# smd-reflow-2-rendered.net
KiCad netlist of a schematic drawn in EAGLE
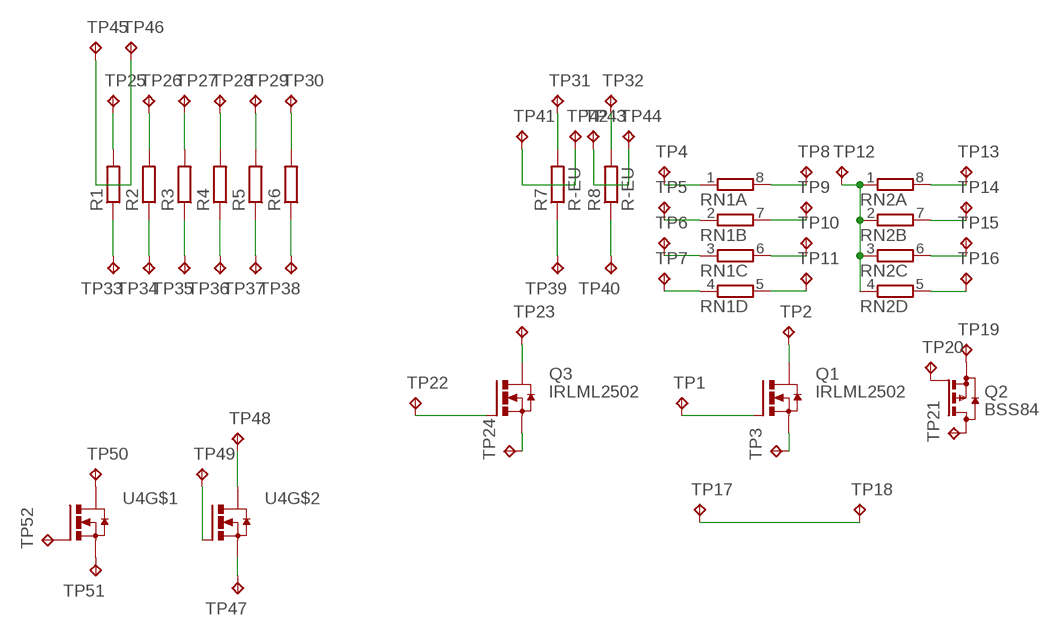
[diagram p0: schematic, sheet 1]

(export (version "E")
  (design (tool "Eeschema 10.0.6"))
  (components
    (comp (ref "Q1")
      (value "IRLML2502")
      (footprint "eagle-import:MICRO3")
      (libsource (lib "eagle-import") (part "IRLML2502"))
    )
    (comp (ref "Q2")
      (value "BSS84")
      (footprint "eagle-import:SOT23")
      (libsource (lib "eagle-import") (part "BSS84"))
    )
    (comp (ref "Q3")
      (value "IRLML2502")
      (footprint "eagle-import:MICRO3")
      (libsource (lib "eagle-import") (part "IRLML2502"))
    )
    (comp (ref "R1")
      (value "R-EU_R0603")
      (footprint "eagle-import:R0603")
      (libsource (lib "eagle-import") (part "R-EU_R0603"))
    )
    (comp (ref "R2")
      (value "R-EU_R0603")
      (footprint "eagle-import:R0603")
      (libsource (lib "eagle-import") (part "R-EU_R0603"))
    )
    (comp (ref "R3")
      (value "R-EU_R0805")
      (footprint "eagle-import:R0805")
      (libsource (lib "eagle-import") (part "R-EU_R0805"))
    )
    (comp (ref "R4")
      (value "R-EU_R0805")
      (footprint "eagle-import:R0805")
      (libsource (lib "eagle-import") (part "R-EU_R0805"))
    )
    (comp (ref "R5")
      (value "R-EU_R0805W")
      (footprint "eagle-import:R0805W")
      (libsource (lib "eagle-import") (part "R-EU_R0805W"))
    )
    (comp (ref "R6")
      (value "R-EU_R0805W")
      (footprint "eagle-import:R0805W")
      (libsource (lib "eagle-import") (part "R-EU_R0805W"))
    )
    (comp (ref "R7")
      (value "R-EU")
      (footprint "eagle-import:R0805H")
      (libsource (lib "eagle-import") (part "R-EU"))
    )
    (comp (ref "R8")
      (value "R-EU")
      (footprint "eagle-import:R0805H")
      (libsource (lib "eagle-import") (part "R-EU"))
    )
    (comp (ref "RN1")
      (value "4R-NEXB38V")
      (footprint "eagle-import:EXB38V")
      (libsource (lib "eagle-import") (part "4R-NEXB38V"))
    )
    (comp (ref "RN2")
      (value "4R-NEXB38V")
      (footprint "eagle-import:EXB38V")
      (libsource (lib "eagle-import") (part "4R-NEXB38V"))
    )
    (comp (ref "TP1")
      (value "TPB1,27")
      (footprint "eagle-import:B1,27")
      (libsource (lib "eagle-import") (part "TPB1,27"))
    )
    (comp (ref "TP2")
      (value "TPB1,27")
      (footprint "eagle-import:B1,27")
      (libsource (lib "eagle-import") (part "TPB1,27"))
    )
    (comp (ref "TP3")
      (value "TPB1,27")
      (footprint "eagle-import:B1,27")
      (libsource (lib "eagle-import") (part "TPB1,27"))
    )
    (comp (ref "TP4")
      (value "TPB1,27")
      (footprint "eagle-import:B1,27")
      (libsource (lib "eagle-import") (part "TPB1,27"))
    )
    (comp (ref "TP5")
      (value "TPB1,27")
      (footprint "eagle-import:B1,27")
      (libsource (lib "eagle-import") (part "TPB1,27"))
    )
    (comp (ref "TP6")
      (value "TPB1,27")
      (footprint "eagle-import:B1,27")
      (libsource (lib "eagle-import") (part "TPB1,27"))
    )
    (comp (ref "TP7")
      (value "TPB1,27")
      (footprint "eagle-import:B1,27")
      (libsource (lib "eagle-import") (part "TPB1,27"))
    )
    (comp (ref "TP8")
      (value "TPB1,27")
      (footprint "eagle-import:B1,27")
      (libsource (lib "eagle-import") (part "TPB1,27"))
    )
    (comp (ref "TP9")
      (value "TPB1,27")
      (footprint "eagle-import:B1,27")
      (libsource (lib "eagle-import") (part "TPB1,27"))
    )
    (comp (ref "TP10")
      (value "TPB1,27")
      (footprint "eagle-import:B1,27")
      (libsource (lib "eagle-import") (part "TPB1,27"))
    )
    (comp (ref "TP11")
      (value "TPB1,27")
      (footprint "eagle-import:B1,27")
      (libsource (lib "eagle-import") (part "TPB1,27"))
    )
    (comp (ref "TP12")
      (value "TPB1,27")
      (footprint "eagle-import:B1,27")
      (libsource (lib "eagle-import") (part "TPB1,27"))
    )
    (comp (ref "TP13")
      (value "TPB1,27")
      (footprint "eagle-import:B1,27")
      (libsource (lib "eagle-import") (part "TPB1,27"))
    )
    (comp (ref "TP14")
      (value "TPB1,27")
      (footprint "eagle-import:B1,27")
      (libsource (lib "eagle-import") (part "TPB1,27"))
    )
    (comp (ref "TP15")
      (value "TPB1,27")
      (footprint "eagle-import:B1,27")
      (libsource (lib "eagle-import") (part "TPB1,27"))
    )
    (comp (ref "TP16")
      (value "TPB1,27")
      (footprint "eagle-import:B1,27")
      (libsource (lib "eagle-import") (part "TPB1,27"))
    )
    (comp (ref "TP17")
      (value "TPB1,27")
      (footprint "eagle-import:B1,27")
      (libsource (lib "eagle-import") (part "TPB1,27"))
    )
    (comp (ref "TP18")
      (value "TPB1,27")
      (footprint "eagle-import:B1,27")
      (libsource (lib "eagle-import") (part "TPB1,27"))
    )
    (comp (ref "TP19")
      (value "TPB1,27")
      (footprint "eagle-import:B1,27")
      (libsource (lib "eagle-import") (part "TPB1,27"))
    )
    (comp (ref "TP20")
      (value "TPB1,27")
      (footprint "eagle-import:B1,27")
      (libsource (lib "eagle-import") (part "TPB1,27"))
    )
    (comp (ref "TP21")
      (value "TPB1,27")
      (footprint "eagle-import:B1,27")
      (libsource (lib "eagle-import") (part "TPB1,27"))
    )
    (comp (ref "TP22")
      (value "TPB1,27")
      (footprint "eagle-import:B1,27")
      (libsource (lib "eagle-import") (part "TPB1,27"))
    )
    (comp (ref "TP23")
      (value "TPB1,27")
      (footprint "eagle-import:B1,27")
      (libsource (lib "eagle-import") (part "TPB1,27"))
    )
    (comp (ref "TP24")
      (value "TPB1,27")
      (footprint "eagle-import:B1,27")
      (libsource (lib "eagle-import") (part "TPB1,27"))
    )
    (comp (ref "TP25")
      (value "TPB1,27")
      (footprint "eagle-import:B1,27")
      (libsource (lib "eagle-import") (part "TPB1,27"))
    )
    (comp (ref "TP26")
      (value "TPB1,27")
      (footprint "eagle-import:B1,27")
      (libsource (lib "eagle-import") (part "TPB1,27"))
    )
    (comp (ref "TP27")
      (value "TPB1,27")
      (footprint "eagle-import:B1,27")
      (libsource (lib "eagle-import") (part "TPB1,27"))
    )
    (comp (ref "TP28")
      (value "TPB1,27")
      (footprint "eagle-import:B1,27")
      (libsource (lib "eagle-import") (part "TPB1,27"))
    )
    (comp (ref "TP29")
      (value "TPB1,27")
      (footprint "eagle-import:B1,27")
      (libsource (lib "eagle-import") (part "TPB1,27"))
    )
    (comp (ref "TP30")
      (value "TPB1,27")
      (footprint "eagle-import:B1,27")
      (libsource (lib "eagle-import") (part "TPB1,27"))
    )
    (comp (ref "TP31")
      (value "TPB1,27")
      (footprint "eagle-import:B1,27")
      (libsource (lib "eagle-import") (part "TPB1,27"))
    )
    (comp (ref "TP32")
      (value "TPB1,27")
      (footprint "eagle-import:B1,27")
      (libsource (lib "eagle-import") (part "TPB1,27"))
    )
    (comp (ref "TP33")
      (value "TPB1,27")
      (footprint "eagle-import:B1,27")
      (libsource (lib "eagle-import") (part "TPB1,27"))
    )
    (comp (ref "TP34")
      (value "TPB1,27")
      (footprint "eagle-import:B1,27")
      (libsource (lib "eagle-import") (part "TPB1,27"))
    )
    (comp (ref "TP35")
      (value "TPB1,27")
      (footprint "eagle-import:B1,27")
      (libsource (lib "eagle-import") (part "TPB1,27"))
    )
    (comp (ref "TP36")
      (value "TPB1,27")
      (footprint "eagle-import:B1,27")
      (libsource (lib "eagle-import") (part "TPB1,27"))
    )
    (comp (ref "TP37")
      (value "TPB1,27")
      (footprint "eagle-import:B1,27")
      (libsource (lib "eagle-import") (part "TPB1,27"))
    )
    (comp (ref "TP38")
      (value "TPB1,27")
      (footprint "eagle-import:B1,27")
      (libsource (lib "eagle-import") (part "TPB1,27"))
    )
    (comp (ref "TP39")
      (value "TPB1,27")
      (footprint "eagle-import:B1,27")
      (libsource (lib "eagle-import") (part "TPB1,27"))
    )
    (comp (ref "TP40")
      (value "TPB1,27")
      (footprint "eagle-import:B1,27")
      (libsource (lib "eagle-import") (part "TPB1,27"))
    )
    (comp (ref "TP41")
      (value "TPB1,27")
      (footprint "eagle-import:B1,27")
      (libsource (lib "eagle-import") (part "TPB1,27"))
    )
    (comp (ref "TP42")
      (value "TPB1,27")
      (footprint "eagle-import:B1,27")
      (libsource (lib "eagle-import") (part "TPB1,27"))
    )
    (comp (ref "TP43")
      (value "TPB1,27")
      (footprint "eagle-import:B1,27")
      (libsource (lib "eagle-import") (part "TPB1,27"))
    )
    (comp (ref "TP44")
      (value "TPB1,27")
      (footprint "eagle-import:B1,27")
      (libsource (lib "eagle-import") (part "TPB1,27"))
    )
    (comp (ref "TP45")
      (value "TPB1,27")
      (footprint "eagle-import:B1,27")
      (libsource (lib "eagle-import") (part "TPB1,27"))
    )
    (comp (ref "TP46")
      (value "TPB1,27")
      (footprint "eagle-import:B1,27")
      (libsource (lib "eagle-import") (part "TPB1,27"))
    )
    (comp (ref "TP47")
      (value "TPB1,27")
      (footprint "eagle-import:B1,27")
      (libsource (lib "eagle-import") (part "TPB1,27"))
    )
    (comp (ref "TP48")
      (value "TPB1,27")
      (footprint "eagle-import:B1,27")
      (libsource (lib "eagle-import") (part "TPB1,27"))
    )
    (comp (ref "TP49")
      (value "TPB1,27")
      (footprint "eagle-import:B1,27")
      (libsource (lib "eagle-import") (part "TPB1,27"))
    )
    (comp (ref "TP50")
      (value "TPB1,27")
      (footprint "eagle-import:B1,27")
      (libsource (lib "eagle-import") (part "TPB1,27"))
    )
    (comp (ref "TP51")
      (value "TPB1,27")
      (footprint "eagle-import:B1,27")
      (libsource (lib "eagle-import") (part "TPB1,27"))
    )
    (comp (ref "TP52")
      (value "TPB1,27")
      (footprint "eagle-import:B1,27")
      (libsource (lib "eagle-import") (part "TPB1,27"))
    )
    (comp (ref "U4")
      (value "2N7002GW")
      (footprint "eagle-import:SOT363_INFINEON")
      (libsource (lib "eagle-import") (part "2N7002GW"))
    )
  )
  (nets
    (net (code "1") (name "Net-(Q1-D)") (class "Default")
      (node (ref "Q1") (pin "3") (pinfunction "D_3") (pintype "passive"))
      (node (ref "TP2") (pin "TP") (pinfunction "TP_TP") (pintype "input"))
    )
    (net (code "2") (name "Net-(Q1-G)") (class "Default")
      (node (ref "Q1") (pin "1") (pinfunction "G_1") (pintype "passive"))
      (node (ref "TP1") (pin "TP") (pinfunction "TP_TP") (pintype "input"))
    )
    (net (code "3") (name "Net-(Q1-S)") (class "Default")
      (node (ref "Q1") (pin "2") (pinfunction "S_2") (pintype "passive"))
      (node (ref "TP3") (pin "TP") (pinfunction "TP_TP") (pintype "input"))
    )
    (net (code "4") (name "Net-(Q2-D)") (class "Default")
      (node (ref "Q2") (pin "3") (pinfunction "D_3") (pintype "passive"))
      (node (ref "TP21") (pin "TP") (pinfunction "TP_TP") (pintype "input"))
    )
    (net (code "5") (name "Net-(Q2-G)") (class "Default")
      (node (ref "Q2") (pin "1") (pinfunction "G_1") (pintype "passive"))
      (node (ref "TP20") (pin "TP") (pinfunction "TP_TP") (pintype "input"))
    )
    (net (code "6") (name "Net-(Q2-S)") (class "Default")
      (node (ref "Q2") (pin "2") (pinfunction "S_2") (pintype "passive"))
      (node (ref "TP19") (pin "TP") (pinfunction "TP_TP") (pintype "input"))
    )
    (net (code "7") (name "Net-(Q3-D)") (class "Default")
      (node (ref "Q3") (pin "3") (pinfunction "D_3") (pintype "passive"))
      (node (ref "TP23") (pin "TP") (pinfunction "TP_TP") (pintype "input"))
    )
    (net (code "8") (name "Net-(Q3-G)") (class "Default")
      (node (ref "Q3") (pin "1") (pinfunction "G_1") (pintype "passive"))
      (node (ref "TP22") (pin "TP") (pinfunction "TP_TP") (pintype "input"))
    )
    (net (code "9") (name "Net-(Q3-S)") (class "Default")
      (node (ref "Q3") (pin "2") (pinfunction "S_2") (pintype "passive"))
      (node (ref "TP24") (pin "TP") (pinfunction "TP_TP") (pintype "input"))
    )
    (net (code "10") (name "Net-(R1-Pad1)") (class "Default")
      (node (ref "R1") (pin "1") (pinfunction "1_1") (pintype "passive"))
      (node (ref "TP33") (pin "TP") (pinfunction "TP_TP") (pintype "input"))
    )
    (net (code "11") (name "Net-(R1-Pad2)") (class "Default")
      (node (ref "R1") (pin "2") (pinfunction "2_2") (pintype "passive"))
      (node (ref "TP25") (pin "TP") (pinfunction "TP_TP") (pintype "input"))
    )
    (net (code "12") (name "Net-(R2-Pad1)") (class "Default")
      (node (ref "R2") (pin "1") (pinfunction "1_1") (pintype "passive"))
      (node (ref "TP34") (pin "TP") (pinfunction "TP_TP") (pintype "input"))
    )
    (net (code "13") (name "Net-(R2-Pad2)") (class "Default")
      (node (ref "R2") (pin "2") (pinfunction "2_2") (pintype "passive"))
      (node (ref "TP26") (pin "TP") (pinfunction "TP_TP") (pintype "input"))
    )
    (net (code "14") (name "Net-(R3-Pad1)") (class "Default")
      (node (ref "R3") (pin "1") (pinfunction "1_1") (pintype "passive"))
      (node (ref "TP35") (pin "TP") (pinfunction "TP_TP") (pintype "input"))
    )
    (net (code "15") (name "Net-(R3-Pad2)") (class "Default")
      (node (ref "R3") (pin "2") (pinfunction "2_2") (pintype "passive"))
      (node (ref "TP27") (pin "TP") (pinfunction "TP_TP") (pintype "input"))
    )
    (net (code "16") (name "Net-(R4-Pad1)") (class "Default")
      (node (ref "R4") (pin "1") (pinfunction "1_1") (pintype "passive"))
      (node (ref "TP36") (pin "TP") (pinfunction "TP_TP") (pintype "input"))
    )
    (net (code "17") (name "Net-(R4-Pad2)") (class "Default")
      (node (ref "R4") (pin "2") (pinfunction "2_2") (pintype "passive"))
      (node (ref "TP28") (pin "TP") (pinfunction "TP_TP") (pintype "input"))
    )
    (net (code "18") (name "Net-(R5-Pad1)") (class "Default")
      (node (ref "R5") (pin "1") (pinfunction "1_1") (pintype "passive"))
      (node (ref "TP37") (pin "TP") (pinfunction "TP_TP") (pintype "input"))
    )
    (net (code "19") (name "Net-(R5-Pad2)") (class "Default")
      (node (ref "R5") (pin "2") (pinfunction "2_2") (pintype "passive"))
      (node (ref "TP29") (pin "TP") (pinfunction "TP_TP") (pintype "input"))
    )
    (net (code "20") (name "Net-(R6-Pad1)") (class "Default")
      (node (ref "R6") (pin "1") (pinfunction "1_1") (pintype "passive"))
      (node (ref "TP38") (pin "TP") (pinfunction "TP_TP") (pintype "input"))
    )
    (net (code "21") (name "Net-(R6-Pad2)") (class "Default")
      (node (ref "R6") (pin "2") (pinfunction "2_2") (pintype "passive"))
      (node (ref "TP30") (pin "TP") (pinfunction "TP_TP") (pintype "input"))
    )
    (net (code "22") (name "Net-(R7-Pad1)") (class "Default")
      (node (ref "R7") (pin "1") (pinfunction "1_1") (pintype "passive"))
      (node (ref "TP39") (pin "TP") (pinfunction "TP_TP") (pintype "input"))
    )
    (net (code "23") (name "Net-(R7-Pad2)") (class "Default")
      (node (ref "R7") (pin "2") (pinfunction "2_2") (pintype "passive"))
      (node (ref "TP31") (pin "TP") (pinfunction "TP_TP") (pintype "input"))
    )
    (net (code "24") (name "Net-(R8-Pad1)") (class "Default")
      (node (ref "R8") (pin "1") (pinfunction "1_1") (pintype "passive"))
      (node (ref "TP40") (pin "TP") (pinfunction "TP_TP") (pintype "input"))
    )
    (net (code "25") (name "Net-(R8-Pad2)") (class "Default")
      (node (ref "R8") (pin "2") (pinfunction "2_2") (pintype "passive"))
      (node (ref "TP32") (pin "TP") (pinfunction "TP_TP") (pintype "input"))
    )
    (net (code "26") (name "Net-(RN1-Pad1)") (class "Default")
      (node (ref "RN1") (pin "1") (pinfunction "1_1") (pintype "passive"))
      (node (ref "TP4") (pin "TP") (pinfunction "TP_TP") (pintype "input"))
    )
    (net (code "27") (name "Net-(RN1A-2)") (class "Default")
      (node (ref "RN1") (pin "8") (pinfunction "2_8") (pintype "passive"))
      (node (ref "TP8") (pin "TP") (pinfunction "TP_TP") (pintype "input"))
    )
    (net (code "28") (name "Net-(RN1B-1)") (class "Default")
      (node (ref "RN1") (pin "2") (pinfunction "1_2") (pintype "passive"))
      (node (ref "TP5") (pin "TP") (pinfunction "TP_TP") (pintype "input"))
    )
    (net (code "29") (name "Net-(RN1B-2)") (class "Default")
      (node (ref "RN1") (pin "7") (pinfunction "2_7") (pintype "passive"))
      (node (ref "TP9") (pin "TP") (pinfunction "TP_TP") (pintype "input"))
    )
    (net (code "30") (name "Net-(RN1C-1)") (class "Default")
      (node (ref "RN1") (pin "3") (pinfunction "1_3") (pintype "passive"))
      (node (ref "TP6") (pin "TP") (pinfunction "TP_TP") (pintype "input"))
    )
    (net (code "31") (name "Net-(RN1C-2)") (class "Default")
      (node (ref "RN1") (pin "6") (pinfunction "2_6") (pintype "passive"))
      (node (ref "TP10") (pin "TP") (pinfunction "TP_TP") (pintype "input"))
    )
    (net (code "32") (name "Net-(RN1D-1)") (class "Default")
      (node (ref "RN1") (pin "4") (pinfunction "1_4") (pintype "passive"))
      (node (ref "TP7") (pin "TP") (pinfunction "TP_TP") (pintype "input"))
    )
    (net (code "33") (name "Net-(RN1D-2)") (class "Default")
      (node (ref "RN1") (pin "5") (pinfunction "2_5") (pintype "passive"))
      (node (ref "TP11") (pin "TP") (pinfunction "TP_TP") (pintype "input"))
    )
    (net (code "34") (name "Net-(RN2A-2)") (class "Default")
      (node (ref "RN2") (pin "8") (pinfunction "2_8") (pintype "passive"))
      (node (ref "TP13") (pin "TP") (pinfunction "TP_TP") (pintype "input"))
    )
    (net (code "35") (name "Net-(RN2B-1)") (class "Default")
      (node (ref "RN2") (pin "1") (pinfunction "1_1") (pintype "passive"))
      (node (ref "RN2") (pin "2") (pinfunction "1_2") (pintype "passive"))
      (node (ref "RN2") (pin "3") (pinfunction "1_3") (pintype "passive"))
      (node (ref "RN2") (pin "4") (pinfunction "1_4") (pintype "passive"))
      (node (ref "TP12") (pin "TP") (pinfunction "TP_TP") (pintype "input"))
    )
    (net (code "36") (name "Net-(RN2B-2)") (class "Default")
      (node (ref "RN2") (pin "7") (pinfunction "2_7") (pintype "passive"))
      (node (ref "TP14") (pin "TP") (pinfunction "TP_TP") (pintype "input"))
    )
    (net (code "37") (name "Net-(RN2C-2)") (class "Default")
      (node (ref "RN2") (pin "6") (pinfunction "2_6") (pintype "passive"))
      (node (ref "TP15") (pin "TP") (pinfunction "TP_TP") (pintype "input"))
    )
    (net (code "38") (name "Net-(RN2D-2)") (class "Default")
      (node (ref "RN2") (pin "5") (pinfunction "2_5") (pintype "passive"))
      (node (ref "TP16") (pin "TP") (pinfunction "TP_TP") (pintype "input"))
    )
    (net (code "39") (name "Net-(TP17-PadTP)") (class "Default")
      (node (ref "TP17") (pin "TP") (pinfunction "TP_TP") (pintype "input"))
      (node (ref "TP18") (pin "TP") (pinfunction "TP_TP") (pintype "input"))
    )
    (net (code "40") (name "Net-(TP41-PadTP)") (class "Default")
      (node (ref "TP41") (pin "TP") (pinfunction "TP_TP") (pintype "input"))
      (node (ref "TP42") (pin "TP") (pinfunction "TP_TP") (pintype "input"))
    )
    (net (code "41") (name "Net-(TP43-PadTP)") (class "Default")
      (node (ref "TP43") (pin "TP") (pinfunction "TP_TP") (pintype "input"))
      (node (ref "TP44") (pin "TP") (pinfunction "TP_TP") (pintype "input"))
    )
    (net (code "42") (name "Net-(TP45-PadTP)") (class "Default")
      (node (ref "TP45") (pin "TP") (pinfunction "TP_TP") (pintype "input"))
      (node (ref "TP46") (pin "TP") (pinfunction "TP_TP") (pintype "input"))
    )
    (net (code "43") (name "Net-(U4A-D)") (class "Default")
      (node (ref "TP50") (pin "TP") (pinfunction "TP_TP") (pintype "input"))
      (node (ref "U4") (pin "6") (pinfunction "D_6") (pintype "passive"))
    )
    (net (code "44") (name "Net-(U4A-G)") (class "Default")
      (node (ref "TP52") (pin "TP") (pinfunction "TP_TP") (pintype "input"))
      (node (ref "U4") (pin "2") (pinfunction "G_2") (pintype "passive"))
    )
    (net (code "45") (name "Net-(U4A-S)") (class "Default")
      (node (ref "TP51") (pin "TP") (pinfunction "TP_TP") (pintype "input"))
      (node (ref "U4") (pin "1") (pinfunction "S_1") (pintype "passive"))
    )
    (net (code "46") (name "Net-(U4B-D)") (class "Default")
      (node (ref "TP48") (pin "TP") (pinfunction "TP_TP") (pintype "input"))
      (node (ref "U4") (pin "3") (pinfunction "D_3") (pintype "passive"))
    )
    (net (code "47") (name "Net-(U4B-G)") (class "Default")
      (node (ref "TP49") (pin "TP") (pinfunction "TP_TP") (pintype "input"))
      (node (ref "U4") (pin "5") (pinfunction "G_5") (pintype "passive"))
    )
    (net (code "48") (name "Net-(U4B-S)") (class "Default")
      (node (ref "TP47") (pin "TP") (pinfunction "TP_TP") (pintype "input"))
      (node (ref "U4") (pin "4") (pinfunction "S_4") (pintype "passive"))
    )
  )
)
